# CLK_INPUT.net
KiCad netlist of a schematic drawn in Altium Designer
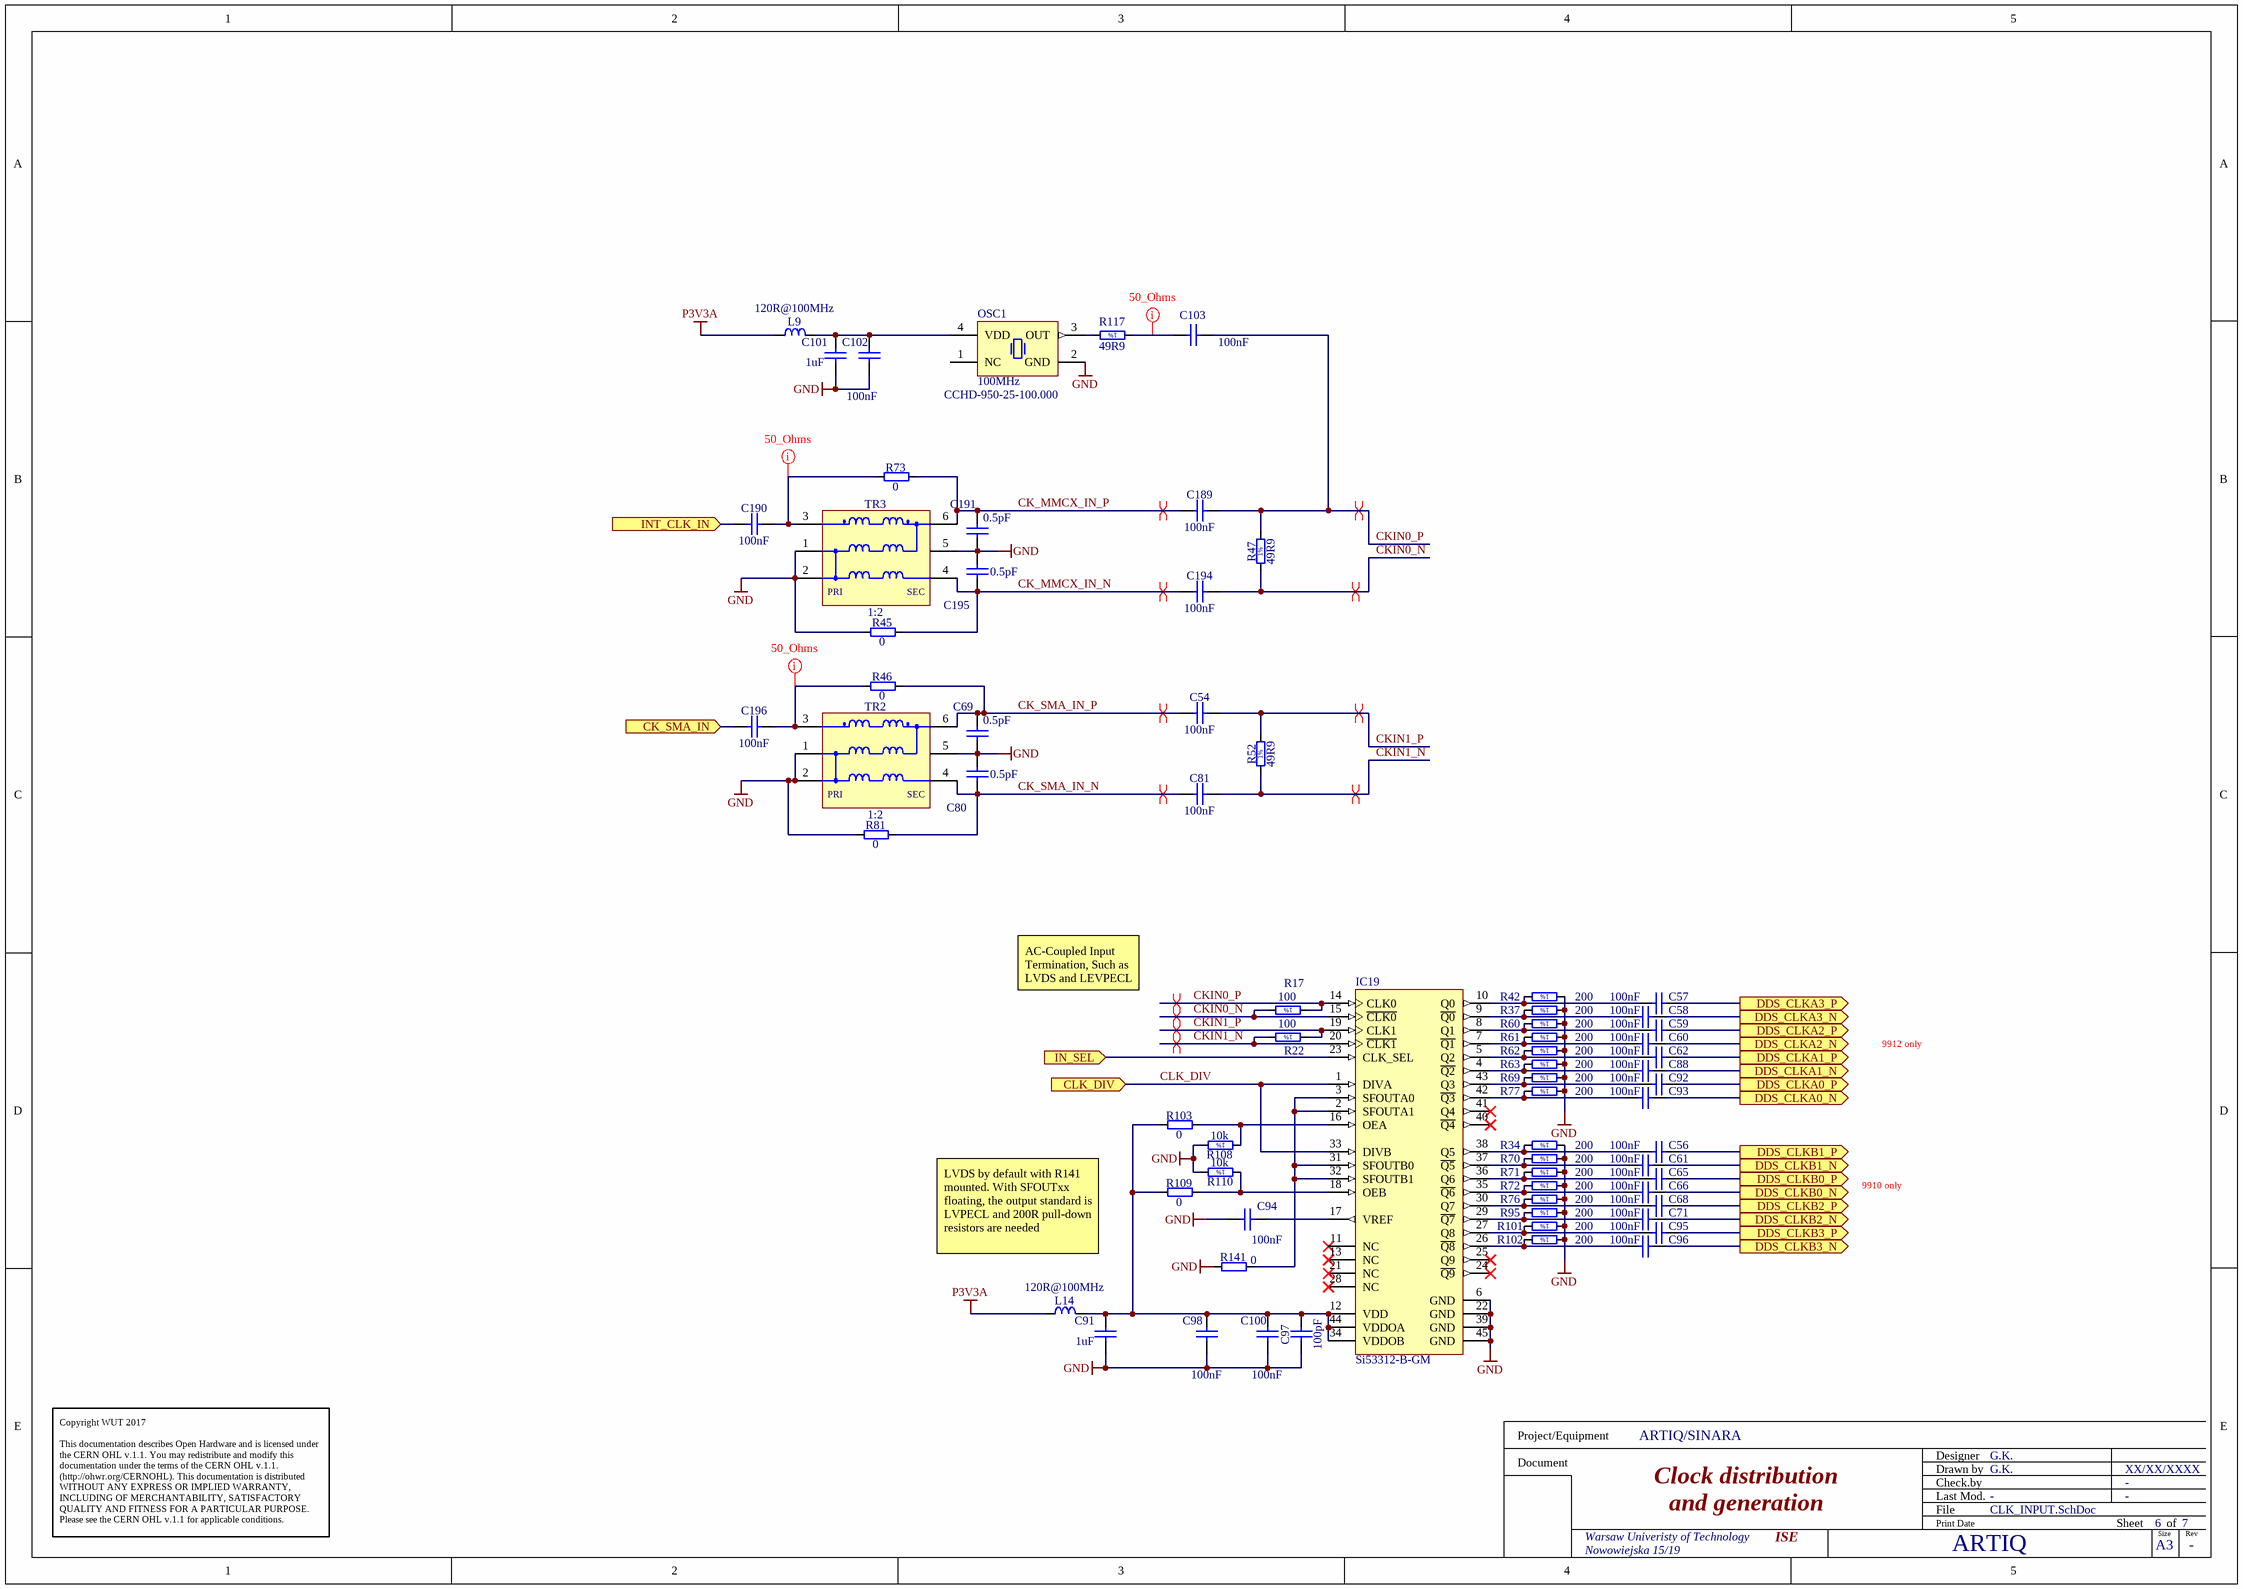
[diagram p0: CLK_INPUT.SchDoc]

(export (version "E")
  (design (tool "Eeschema 10.0.6"))
  (components
    (comp (ref "C54")
      (value "100nF")
      (footprint "CAPC1005X55N")
      (description "Non-polarised capacitor")
      (fields
        (field (name "PART NUMBER") "CC0402_100NF_16V_10%_X5R")
        (field (name "VOLTAGE") "16V")
        (field (name "AUTHOR") "CERN DEM JLC")
      )
      (libsource (lib "Capacitors") (part "Capacitor - non polarized"))
    )
    (comp (ref "C56")
      (value "100nF")
      (footprint "CAPC1005X55N")
      (description "Non-polarised capacitor")
      (fields
        (field (name "PART NUMBER") "CC0402_100NF_16V_10%_X5R")
        (field (name "VOLTAGE") "16V")
        (field (name "AUTHOR") "CERN DEM JLC")
      )
      (libsource (lib "Capacitors") (part "Capacitor - non polarized"))
    )
    (comp (ref "C57")
      (value "100nF")
      (footprint "CAPC1005X55N")
      (description "Non-polarised capacitor")
      (fields
        (field (name "PART NUMBER") "CC0402_100NF_16V_10%_X5R")
        (field (name "VOLTAGE") "16V")
        (field (name "AUTHOR") "CERN DEM JLC")
      )
      (libsource (lib "Capacitors") (part "Capacitor - non polarized"))
    )
    (comp (ref "C58")
      (value "100nF")
      (footprint "CAPC1005X55N")
      (description "Non-polarised capacitor")
      (fields
        (field (name "PART NUMBER") "CC0402_100NF_16V_10%_X5R")
        (field (name "VOLTAGE") "16V")
        (field (name "AUTHOR") "CERN DEM JLC")
      )
      (libsource (lib "Capacitors") (part "Capacitor - non polarized"))
    )
    (comp (ref "C59")
      (value "100nF")
      (footprint "CAPC1005X55N")
      (description "Non-polarised capacitor")
      (fields
        (field (name "PART NUMBER") "CC0402_100NF_16V_10%_X5R")
        (field (name "VOLTAGE") "16V")
        (field (name "AUTHOR") "CERN DEM JLC")
      )
      (libsource (lib "Capacitors") (part "Capacitor - non polarized"))
    )
    (comp (ref "C60")
      (value "100nF")
      (footprint "CAPC1005X55N")
      (description "Non-polarised capacitor")
      (fields
        (field (name "PART NUMBER") "CC0402_100NF_16V_10%_X5R")
        (field (name "VOLTAGE") "16V")
        (field (name "AUTHOR") "CERN DEM JLC")
      )
      (libsource (lib "Capacitors") (part "Capacitor - non polarized"))
    )
    (comp (ref "C61")
      (value "100nF")
      (footprint "CAPC1005X55N")
      (description "Non-polarised capacitor")
      (fields
        (field (name "PART NUMBER") "CC0402_100NF_16V_10%_X5R")
        (field (name "VOLTAGE") "16V")
        (field (name "AUTHOR") "CERN DEM JLC")
      )
      (libsource (lib "Capacitors") (part "Capacitor - non polarized"))
    )
    (comp (ref "C62")
      (value "100nF")
      (footprint "CAPC1005X55N")
      (description "Non-polarised capacitor")
      (fields
        (field (name "PART NUMBER") "CC0402_100NF_16V_10%_X5R")
        (field (name "VOLTAGE") "16V")
        (field (name "AUTHOR") "CERN DEM JLC")
      )
      (libsource (lib "Capacitors") (part "Capacitor - non polarized"))
    )
    (comp (ref "C65")
      (value "100nF")
      (footprint "CAPC1005X55N")
      (description "Non-polarised capacitor")
      (fields
        (field (name "PART NUMBER") "CC0402_100NF_16V_10%_X5R")
        (field (name "VOLTAGE") "16V")
        (field (name "AUTHOR") "CERN DEM JLC")
      )
      (libsource (lib "Capacitors") (part "Capacitor - non polarized"))
    )
    (comp (ref "C66")
      (value "100nF")
      (footprint "CAPC1005X55N")
      (description "Non-polarised capacitor")
      (fields
        (field (name "PART NUMBER") "CC0402_100NF_16V_10%_X5R")
        (field (name "VOLTAGE") "16V")
        (field (name "AUTHOR") "CERN DEM JLC")
      )
      (libsource (lib "Capacitors") (part "Capacitor - non polarized"))
    )
    (comp (ref "C68")
      (value "100nF")
      (footprint "CAPC1005X55N")
      (description "Non-polarised capacitor")
      (fields
        (field (name "PART NUMBER") "CC0402_100NF_16V_10%_X5R")
        (field (name "VOLTAGE") "16V")
        (field (name "AUTHOR") "CERN DEM JLC")
      )
      (libsource (lib "Capacitors") (part "Capacitor - non polarized"))
    )
    (comp (ref "C69")
      (value "0.5pF")
      (footprint "CAPC1005X50N")
      (description "Non-polarised capacitor")
      (fields
        (field (name "PART NUMBER") "CC0402_0.5PF_25V_0.05PF_AVX_04023J0R5ABSTR")
        (field (name "VOLTAGE") "25V")
        (field (name "AUTHOR") "CERN DEM JLC")
      )
      (libsource (lib "Capacitors") (part "Capacitor - non polarized"))
    )
    (comp (ref "C71")
      (value "100nF")
      (footprint "CAPC1005X55N")
      (description "Non-polarised capacitor")
      (fields
        (field (name "PART NUMBER") "CC0402_100NF_16V_10%_X5R")
        (field (name "VOLTAGE") "16V")
        (field (name "AUTHOR") "CERN DEM JLC")
      )
      (libsource (lib "Capacitors") (part "Capacitor - non polarized"))
    )
    (comp (ref "C80")
      (value "0.5pF")
      (footprint "CAPC1005X50N")
      (description "Non-polarised capacitor")
      (fields
        (field (name "PART NUMBER") "CC0402_0.5PF_25V_0.05PF_AVX_04023J0R5ABSTR")
        (field (name "VOLTAGE") "25V")
        (field (name "AUTHOR") "CERN DEM JLC")
      )
      (libsource (lib "Capacitors") (part "Capacitor - non polarized"))
    )
    (comp (ref "C81")
      (value "100nF")
      (footprint "CAPC1005X55N")
      (description "Non-polarised capacitor")
      (fields
        (field (name "PART NUMBER") "CC0402_100NF_16V_10%_X5R")
        (field (name "VOLTAGE") "16V")
        (field (name "AUTHOR") "CERN DEM JLC")
      )
      (libsource (lib "Capacitors") (part "Capacitor - non polarized"))
    )
    (comp (ref "C88")
      (value "100nF")
      (footprint "CAPC1005X55N")
      (description "Non-polarised capacitor")
      (fields
        (field (name "PART NUMBER") "CC0402_100NF_16V_10%_X5R")
        (field (name "VOLTAGE") "16V")
        (field (name "AUTHOR") "CERN DEM JLC")
      )
      (libsource (lib "Capacitors") (part "Capacitor - non polarized"))
    )
    (comp (ref "C91")
      (value "1uF")
      (footprint "CAPC1005X55N")
      (description "Non-polarised capacitor")
      (fields
        (field (name "PART NUMBER") "CC0402_1UF_16V_10%_X5R")
        (field (name "VOLTAGE") "16V")
        (field (name "AUTHOR") "CERN DEM JLC")
      )
      (libsource (lib "Capacitors") (part "Capacitor - non polarized"))
    )
    (comp (ref "C92")
      (value "100nF")
      (footprint "CAPC1005X55N")
      (description "Non-polarised capacitor")
      (fields
        (field (name "PART NUMBER") "CC0402_100NF_16V_10%_X5R")
        (field (name "VOLTAGE") "16V")
        (field (name "AUTHOR") "CERN DEM JLC")
      )
      (libsource (lib "Capacitors") (part "Capacitor - non polarized"))
    )
    (comp (ref "C93")
      (value "100nF")
      (footprint "CAPC1005X55N")
      (description "Non-polarised capacitor")
      (fields
        (field (name "PART NUMBER") "CC0402_100NF_16V_10%_X5R")
        (field (name "VOLTAGE") "16V")
        (field (name "AUTHOR") "CERN DEM JLC")
      )
      (libsource (lib "Capacitors") (part "Capacitor - non polarized"))
    )
    (comp (ref "C94")
      (value "100nF")
      (footprint "CAPC1005X55N")
      (description "Non-polarised capacitor")
      (fields
        (field (name "PART NUMBER") "CC0402_100NF_16V_10%_X5R")
        (field (name "VOLTAGE") "16V")
        (field (name "AUTHOR") "CERN DEM JLC")
      )
      (libsource (lib "Capacitors") (part "Capacitor - non polarized"))
    )
    (comp (ref "C95")
      (value "100nF")
      (footprint "CAPC1005X55N")
      (description "Non-polarised capacitor")
      (fields
        (field (name "PART NUMBER") "CC0402_100NF_16V_10%_X5R")
        (field (name "VOLTAGE") "16V")
        (field (name "AUTHOR") "CERN DEM JLC")
      )
      (libsource (lib "Capacitors") (part "Capacitor - non polarized"))
    )
    (comp (ref "C96")
      (value "100nF")
      (footprint "CAPC1005X55N")
      (description "Non-polarised capacitor")
      (fields
        (field (name "PART NUMBER") "CC0402_100NF_16V_10%_X5R")
        (field (name "VOLTAGE") "16V")
        (field (name "AUTHOR") "CERN DEM JLC")
      )
      (libsource (lib "Capacitors") (part "Capacitor - non polarized"))
    )
    (comp (ref "C97")
      (value "100pF")
      (footprint "CAPC1005X55N")
      (description "Non-polarised capacitor")
      (fields
        (field (name "PART NUMBER") "CC0402_100PF_50V_5%_C0G")
        (field (name "VOLTAGE") "50V")
        (field (name "AUTHOR") "CERN DEM JLC")
      )
      (libsource (lib "Capacitors") (part "Capacitor - non polarized"))
    )
    (comp (ref "C98")
      (value "100nF")
      (footprint "CAPC1005X55N")
      (description "Non-polarised capacitor")
      (fields
        (field (name "PART NUMBER") "CC0402_100NF_16V_10%_X5R")
        (field (name "VOLTAGE") "16V")
        (field (name "AUTHOR") "CERN DEM JLC")
      )
      (libsource (lib "Capacitors") (part "Capacitor - non polarized"))
    )
    (comp (ref "C100")
      (value "100nF")
      (footprint "CAPC1005X55N")
      (description "Non-polarised capacitor")
      (fields
        (field (name "PART NUMBER") "CC0402_100NF_16V_10%_X5R")
        (field (name "VOLTAGE") "16V")
        (field (name "AUTHOR") "CERN DEM JLC")
      )
      (libsource (lib "Capacitors") (part "Capacitor - non polarized"))
    )
    (comp (ref "C101")
      (value "1uF")
      (footprint "CAPC1005X55N")
      (description "Non-polarised capacitor")
      (fields
        (field (name "PART NUMBER") "CC0402_1UF_16V_10%_X5R")
        (field (name "VOLTAGE") "16V")
        (field (name "AUTHOR") "CERN DEM JLC")
      )
      (libsource (lib "Capacitors") (part "Capacitor - non polarized"))
    )
    (comp (ref "C102")
      (value "100nF")
      (footprint "CAPC1005X55N")
      (description "Non-polarised capacitor")
      (fields
        (field (name "PART NUMBER") "CC0402_100NF_16V_10%_X5R")
        (field (name "VOLTAGE") "16V")
        (field (name "AUTHOR") "CERN DEM JLC")
      )
      (libsource (lib "Capacitors") (part "Capacitor - non polarized"))
    )
    (comp (ref "C103")
      (value "100nF")
      (footprint "CAPC1005X55N")
      (description "Non-polarised capacitor")
      (fields
        (field (name "PART NUMBER") "CC0402_100NF_16V_10%_X5R")
        (field (name "VOLTAGE") "16V")
        (field (name "AUTHOR") "CERN DEM JLC")
      )
      (libsource (lib "Capacitors") (part "Capacitor - non polarized"))
    )
    (comp (ref "C189")
      (value "100nF")
      (footprint "CAPC1005X55N")
      (description "Non-polarised capacitor")
      (fields
        (field (name "PART NUMBER") "CC0402_100NF_16V_10%_X5R")
        (field (name "VOLTAGE") "16V")
        (field (name "AUTHOR") "CERN DEM JLC")
      )
      (libsource (lib "Capacitors") (part "Capacitor - non polarized"))
    )
    (comp (ref "C190")
      (value "100nF")
      (footprint "CAPC1005X55N")
      (description "Non-polarised capacitor")
      (fields
        (field (name "PART NUMBER") "CC0402_100NF_16V_10%_X5R")
        (field (name "VOLTAGE") "16V")
        (field (name "AUTHOR") "CERN DEM JLC")
      )
      (libsource (lib "Capacitors") (part "Capacitor - non polarized"))
    )
    (comp (ref "C191")
      (value "0.5pF")
      (footprint "CAPC1005X50N")
      (description "Non-polarised capacitor")
      (fields
        (field (name "PART NUMBER") "CC0402_0.5PF_25V_0.05PF_AVX_04023J0R5ABSTR")
        (field (name "VOLTAGE") "25V")
        (field (name "AUTHOR") "CERN DEM JLC")
      )
      (libsource (lib "Capacitors") (part "Capacitor - non polarized"))
    )
    (comp (ref "C194")
      (value "100nF")
      (footprint "CAPC1005X55N")
      (description "Non-polarised capacitor")
      (fields
        (field (name "PART NUMBER") "CC0402_100NF_16V_10%_X5R")
        (field (name "VOLTAGE") "16V")
        (field (name "AUTHOR") "CERN DEM JLC")
      )
      (libsource (lib "Capacitors") (part "Capacitor - non polarized"))
    )
    (comp (ref "C195")
      (value "0.5pF")
      (footprint "CAPC1005X50N")
      (description "Non-polarised capacitor")
      (fields
        (field (name "PART NUMBER") "CC0402_0.5PF_25V_0.05PF_AVX_04023J0R5ABSTR")
        (field (name "VOLTAGE") "25V")
        (field (name "AUTHOR") "CERN DEM JLC")
      )
      (libsource (lib "Capacitors") (part "Capacitor - non polarized"))
    )
    (comp (ref "C196")
      (value "100nF")
      (footprint "CAPC1005X55N")
      (description "Non-polarised capacitor")
      (fields
        (field (name "PART NUMBER") "CC0402_100NF_16V_10%_X5R")
        (field (name "VOLTAGE") "16V")
        (field (name "AUTHOR") "CERN DEM JLC")
      )
      (libsource (lib "Capacitors") (part "Capacitor - non polarized"))
    )
    (comp (ref "IC19")
      (value "Si53312-B-GM")
      (footprint "SLAB-QFN-44-2800x2800TP_N")
      (fields (field (name "MANUFACTURER") "Silicon Labs"))
      (libsource (lib "Altium Content Vault") (part "SLAB-Si53312-QFN-44-45"))
    )
    (comp (ref "L9")
      (value "120R@100MHz")
      (footprint "INDC1608X95N")
      (description "Inductor")
      (fields
        (field (name "PART NUMBER") "IND0603_MURATA_BLM18PG121SN1D")
        (field (name "POWER") "2A")
        (field (name "AUTHOR") "CERN DEM BC")
      )
      (libsource (lib "Inductors & Transformers") (part "Inductor"))
    )
    (comp (ref "L14")
      (value "120R@100MHz")
      (footprint "INDC1608X95N")
      (description "Inductor")
      (fields
        (field (name "PART NUMBER") "IND0603_MURATA_BLM18PG121SN1D")
        (field (name "POWER") "2A")
        (field (name "AUTHOR") "CERN DEM BC")
      )
      (libsource (lib "Inductors & Transformers") (part "Inductor"))
    )
    (comp (ref "OSC1")
      (value "100MHz")
      (footprint "OSC_CRYSTEK_CCHD-950")
      (description "100MHz low noise oscillator")
      (fields
        (field (name "PART NUMBER") "OSC_100MHZ_CRYSTEK_CCHD-950-25-100.000")
        (field (name "MANUFACTURER") "CRYSTEK CRYSTAL")
        (field (name "MANUFACTURER PART NUMBER") "CCHD-950-25-100.000")
        (field (name "AUTHOR") "GK")
      )
      (libsource (lib "LIBRARY_SCH") (part "OSC_CCHD-950"))
    )
    (comp (ref "R17")
      (value "100")
      (footprint "RESC1005X40N")
      (description "Resistor - 1%")
      (fields
        (field (name "PART NUMBER") "R0402_100R_1%_0.0625W_100PPM")
        (field (name "POWER") "0.0625W")
        (field (name "AUTHOR") "CERN DEM JLC")
      )
      (libsource (lib "Resistors") (part "Resistor - 1%"))
    )
    (comp (ref "R22")
      (value "100")
      (footprint "RESC1005X40N")
      (description "Resistor - 1%")
      (fields
        (field (name "PART NUMBER") "R0402_100R_1%_0.0625W_100PPM")
        (field (name "POWER") "0.0625W")
        (field (name "AUTHOR") "CERN DEM JLC")
      )
      (libsource (lib "Resistors") (part "Resistor - 1%"))
    )
    (comp (ref "R34")
      (value "200")
      (footprint "RESC1005X40N")
      (description "Resistor - 1%")
      (fields
        (field (name "PART NUMBER") "R0402_200R_1%_0.0625W_100PPM")
        (field (name "POWER") "0.0625W")
        (field (name "AUTHOR") "CERN DEM JLC")
      )
      (libsource (lib "Resistors") (part "Resistor - 1%"))
    )
    (comp (ref "R37")
      (value "200")
      (footprint "RESC1005X40N")
      (description "Resistor - 1%")
      (fields
        (field (name "PART NUMBER") "R0402_200R_1%_0.0625W_100PPM")
        (field (name "POWER") "0.0625W")
        (field (name "AUTHOR") "CERN DEM JLC")
      )
      (libsource (lib "Resistors") (part "Resistor - 1%"))
    )
    (comp (ref "R42")
      (value "200")
      (footprint "RESC1005X40N")
      (description "Resistor - 1%")
      (fields
        (field (name "PART NUMBER") "R0402_200R_1%_0.0625W_100PPM")
        (field (name "POWER") "0.0625W")
        (field (name "AUTHOR") "CERN DEM JLC")
      )
      (libsource (lib "Resistors") (part "Resistor - 1%"))
    )
    (comp (ref "R45")
      (value "0")
      (footprint "RESC1005X40N")
      (description "Resistor")
      (fields
        (field (name "PART NUMBER") "R0402_0R_JUMPER")
        (field (name "MANUFACTURER") "GENERIC")
        (field (name "AUTHOR") "CERN DEM JLC")
      )
      (libsource (lib "Resistors") (part "Resistor"))
    )
    (comp (ref "R46")
      (value "0")
      (footprint "RESC1005X40N")
      (description "Resistor")
      (fields
        (field (name "PART NUMBER") "R0402_0R_JUMPER")
        (field (name "MANUFACTURER") "GENERIC")
        (field (name "AUTHOR") "CERN DEM JLC")
      )
      (libsource (lib "Resistors") (part "Resistor"))
    )
    (comp (ref "R47")
      (value "49R9")
      (footprint "RESC1005X40N")
      (description "Resistor - 1%")
      (fields
        (field (name "PART NUMBER") "R0402_49R9_1%_0.0625W_100PPM")
        (field (name "POWER") "0.0625W")
        (field (name "AUTHOR") "CERN DEM JLC")
      )
      (libsource (lib "Resistors") (part "Resistor - 1%"))
    )
    (comp (ref "R52")
      (value "49R9")
      (footprint "RESC1005X40N")
      (description "Resistor - 1%")
      (fields
        (field (name "PART NUMBER") "R0402_49R9_1%_0.0625W_100PPM")
        (field (name "POWER") "0.0625W")
        (field (name "AUTHOR") "CERN DEM JLC")
      )
      (libsource (lib "Resistors") (part "Resistor - 1%"))
    )
    (comp (ref "R60")
      (value "200")
      (footprint "RESC1005X40N")
      (description "Resistor - 1%")
      (fields
        (field (name "PART NUMBER") "R0402_200R_1%_0.0625W_100PPM")
        (field (name "POWER") "0.0625W")
        (field (name "AUTHOR") "CERN DEM JLC")
      )
      (libsource (lib "Resistors") (part "Resistor - 1%"))
    )
    (comp (ref "R61")
      (value "200")
      (footprint "RESC1005X40N")
      (description "Resistor - 1%")
      (fields
        (field (name "PART NUMBER") "R0402_200R_1%_0.0625W_100PPM")
        (field (name "POWER") "0.0625W")
        (field (name "AUTHOR") "CERN DEM JLC")
      )
      (libsource (lib "Resistors") (part "Resistor - 1%"))
    )
    (comp (ref "R62")
      (value "200")
      (footprint "RESC1005X40N")
      (description "Resistor - 1%")
      (fields
        (field (name "PART NUMBER") "R0402_200R_1%_0.0625W_100PPM")
        (field (name "POWER") "0.0625W")
        (field (name "AUTHOR") "CERN DEM JLC")
      )
      (libsource (lib "Resistors") (part "Resistor - 1%"))
    )
    (comp (ref "R63")
      (value "200")
      (footprint "RESC1005X40N")
      (description "Resistor - 1%")
      (fields
        (field (name "PART NUMBER") "R0402_200R_1%_0.0625W_100PPM")
        (field (name "POWER") "0.0625W")
        (field (name "AUTHOR") "CERN DEM JLC")
      )
      (libsource (lib "Resistors") (part "Resistor - 1%"))
    )
    (comp (ref "R69")
      (value "200")
      (footprint "RESC1005X40N")
      (description "Resistor - 1%")
      (fields
        (field (name "PART NUMBER") "R0402_200R_1%_0.0625W_100PPM")
        (field (name "POWER") "0.0625W")
        (field (name "AUTHOR") "CERN DEM JLC")
      )
      (libsource (lib "Resistors") (part "Resistor - 1%"))
    )
    (comp (ref "R70")
      (value "200")
      (footprint "RESC1005X40N")
      (description "Resistor - 1%")
      (fields
        (field (name "PART NUMBER") "R0402_200R_1%_0.0625W_100PPM")
        (field (name "POWER") "0.0625W")
        (field (name "AUTHOR") "CERN DEM JLC")
      )
      (libsource (lib "Resistors") (part "Resistor - 1%"))
    )
    (comp (ref "R71")
      (value "200")
      (footprint "RESC1005X40N")
      (description "Resistor - 1%")
      (fields
        (field (name "PART NUMBER") "R0402_200R_1%_0.0625W_100PPM")
        (field (name "POWER") "0.0625W")
        (field (name "AUTHOR") "CERN DEM JLC")
      )
      (libsource (lib "Resistors") (part "Resistor - 1%"))
    )
    (comp (ref "R72")
      (value "200")
      (footprint "RESC1005X40N")
      (description "Resistor - 1%")
      (fields
        (field (name "PART NUMBER") "R0402_200R_1%_0.0625W_100PPM")
        (field (name "POWER") "0.0625W")
        (field (name "AUTHOR") "CERN DEM JLC")
      )
      (libsource (lib "Resistors") (part "Resistor - 1%"))
    )
    (comp (ref "R73")
      (value "0")
      (footprint "RESC1005X40N")
      (description "Resistor")
      (fields
        (field (name "PART NUMBER") "R0402_0R_JUMPER")
        (field (name "MANUFACTURER") "GENERIC")
        (field (name "AUTHOR") "CERN DEM JLC")
      )
      (libsource (lib "Resistors") (part "Resistor"))
    )
    (comp (ref "R76")
      (value "200")
      (footprint "RESC1005X40N")
      (description "Resistor - 1%")
      (fields
        (field (name "PART NUMBER") "R0402_200R_1%_0.0625W_100PPM")
        (field (name "POWER") "0.0625W")
        (field (name "AUTHOR") "CERN DEM JLC")
      )
      (libsource (lib "Resistors") (part "Resistor - 1%"))
    )
    (comp (ref "R77")
      (value "200")
      (footprint "RESC1005X40N")
      (description "Resistor - 1%")
      (fields
        (field (name "PART NUMBER") "R0402_200R_1%_0.0625W_100PPM")
        (field (name "POWER") "0.0625W")
        (field (name "AUTHOR") "CERN DEM JLC")
      )
      (libsource (lib "Resistors") (part "Resistor - 1%"))
    )
    (comp (ref "R81")
      (value "0")
      (footprint "RESC1005X40N")
      (description "Resistor")
      (fields
        (field (name "PART NUMBER") "R0402_0R_JUMPER")
        (field (name "MANUFACTURER") "GENERIC")
        (field (name "AUTHOR") "CERN DEM JLC")
      )
      (libsource (lib "Resistors") (part "Resistor"))
    )
    (comp (ref "R95")
      (value "200")
      (footprint "RESC1005X40N")
      (description "Resistor - 1%")
      (fields
        (field (name "PART NUMBER") "R0402_200R_1%_0.0625W_100PPM")
        (field (name "POWER") "0.0625W")
        (field (name "AUTHOR") "CERN DEM JLC")
      )
      (libsource (lib "Resistors") (part "Resistor - 1%"))
    )
    (comp (ref "R101")
      (value "200")
      (footprint "RESC1005X40N")
      (description "Resistor - 1%")
      (fields
        (field (name "PART NUMBER") "R0402_200R_1%_0.0625W_100PPM")
        (field (name "POWER") "0.0625W")
        (field (name "AUTHOR") "CERN DEM JLC")
      )
      (libsource (lib "Resistors") (part "Resistor - 1%"))
    )
    (comp (ref "R102")
      (value "200")
      (footprint "RESC1005X40N")
      (description "Resistor - 1%")
      (fields
        (field (name "PART NUMBER") "R0402_200R_1%_0.0625W_100PPM")
        (field (name "POWER") "0.0625W")
        (field (name "AUTHOR") "CERN DEM JLC")
      )
      (libsource (lib "Resistors") (part "Resistor - 1%"))
    )
    (comp (ref "R103")
      (value "0")
      (footprint "RESC1608X55N")
      (description "Resistor")
      (fields
        (field (name "PART NUMBER") "R0603_0R_JUMPER")
        (field (name "MANUFACTURER") "GENERIC")
        (field (name "AUTHOR") "CERN DEM JLC")
      )
      (libsource (lib "Resistors") (part "Resistor"))
    )
    (comp (ref "R108")
      (value "10k")
      (footprint "RESC1005X40N")
      (description "Resistor - 1%")
      (fields
        (field (name "PART NUMBER") "R0402_10K_1%_0.0625W_100PPM")
        (field (name "POWER") "0.0625W")
        (field (name "AUTHOR") "CERN DEM JLC")
      )
      (libsource (lib "Resistors") (part "Resistor - 1%"))
    )
    (comp (ref "R109")
      (value "0")
      (footprint "RESC1608X55N")
      (description "Resistor")
      (fields
        (field (name "PART NUMBER") "R0603_0R_JUMPER")
        (field (name "MANUFACTURER") "GENERIC")
        (field (name "AUTHOR") "CERN DEM JLC")
      )
      (libsource (lib "Resistors") (part "Resistor"))
    )
    (comp (ref "R110")
      (value "10k")
      (footprint "RESC1005X40N")
      (description "Resistor - 1%")
      (fields
        (field (name "PART NUMBER") "R0402_10K_1%_0.0625W_100PPM")
        (field (name "POWER") "0.0625W")
        (field (name "AUTHOR") "CERN DEM JLC")
      )
      (libsource (lib "Resistors") (part "Resistor - 1%"))
    )
    (comp (ref "R117")
      (value "49R9")
      (footprint "RESC1005X40N")
      (description "Resistor - 1%")
      (fields
        (field (name "PART NUMBER") "R0402_49R9_1%_0.0625W_100PPM")
        (field (name "POWER") "0.0625W")
        (field (name "AUTHOR") "CERN DEM JLC")
      )
      (libsource (lib "Resistors") (part "Resistor - 1%"))
    )
    (comp (ref "R141")
      (value "0")
      (footprint "RESC1608X55N")
      (description "Resistor")
      (fields
        (field (name "PART NUMBER") "R0603_0R_JUMPER")
        (field (name "MANUFACTURER") "GENERIC")
        (field (name "AUTHOR") "CERN DEM JLC")
      )
      (libsource (lib "Resistors") (part "Resistor"))
    )
    (comp (ref "TR2")
      (value "1:2")
      (footprint "XFMR_MINI-CIRCUITS_DB1627")
      (description "50 OHMS 10 to 4000 MHz RF Transformer")
      (fields
        (field (name "PART NUMBER") "XFMR_MINI-CIRCUITS_TCM2-43X+")
        (field (name "POWER") "0.4W")
        (field (name "AUTHOR") "CERN DEM BC")
      )
      (libsource (lib "Inductors & Transformers") (part "XFMR_MINI-CIRCUITS_TCM2-43X"))
    )
    (comp (ref "TR3")
      (value "1:2")
      (footprint "XFMR_MINI-CIRCUITS_DB1627")
      (description "50 OHMS 10 to 4000 MHz RF Transformer")
      (fields
        (field (name "PART NUMBER") "XFMR_MINI-CIRCUITS_TCM2-43X+")
        (field (name "POWER") "0.4W")
        (field (name "AUTHOR") "CERN DEM BC")
      )
      (libsource (lib "Inductors & Transformers") (part "XFMR_MINI-CIRCUITS_TCM2-43X"))
    )
  )
  (nets
    (net (code "1") (name "/CKIN0_N") (class "Default")
      (node (ref "C194") (pin "2") (pinfunction "2_2") (pintype "passive"))
      (node (ref "IC19") (pin "15") (pinfunction "~{CLK0}_15") (pintype "input"))
      (node (ref "R17") (pin "2") (pinfunction "2_2") (pintype "passive"))
      (node (ref "R47") (pin "1") (pinfunction "1_1") (pintype "passive"))
    )
    (net (code "2") (name "/CKIN0_P") (class "Default")
      (node (ref "C103") (pin "1") (pinfunction "1_1") (pintype "passive"))
      (node (ref "C189") (pin "2") (pinfunction "2_2") (pintype "passive"))
      (node (ref "IC19") (pin "14") (pinfunction "CLK0_14") (pintype "input"))
      (node (ref "R17") (pin "1") (pinfunction "1_1") (pintype "passive"))
      (node (ref "R47") (pin "2") (pinfunction "2_2") (pintype "passive"))
    )
    (net (code "3") (name "/CKIN1_N") (class "Default")
      (node (ref "C81") (pin "2") (pinfunction "2_2") (pintype "passive"))
      (node (ref "IC19") (pin "20") (pinfunction "~{CLK1}_20") (pintype "input"))
      (node (ref "R22") (pin "2") (pinfunction "2_2") (pintype "passive"))
      (node (ref "R52") (pin "1") (pinfunction "1_1") (pintype "passive"))
    )
    (net (code "4") (name "/CKIN1_P") (class "Default")
      (node (ref "C54") (pin "2") (pinfunction "2_2") (pintype "passive"))
      (node (ref "IC19") (pin "19") (pinfunction "CLK1_19") (pintype "input"))
      (node (ref "R22") (pin "1") (pinfunction "1_1") (pintype "passive"))
      (node (ref "R52") (pin "2") (pinfunction "2_2") (pintype "passive"))
    )
    (net (code "5") (name "/CK_MMCX_IN_N") (class "Default")
      (node (ref "C194") (pin "1") (pinfunction "1_1") (pintype "passive"))
      (node (ref "C195") (pin "1") (pinfunction "1_1") (pintype "passive"))
      (node (ref "R45") (pin "2") (pinfunction "2_2") (pintype "passive"))
      (node (ref "TR3") (pin "4") (pinfunction "S1_4") (pintype "passive"))
    )
    (net (code "6") (name "/CK_MMCX_IN_P") (class "Default")
      (node (ref "C189") (pin "1") (pinfunction "1_1") (pintype "passive"))
      (node (ref "C191") (pin "2") (pinfunction "2_2") (pintype "passive"))
      (node (ref "R73") (pin "2") (pinfunction "2_2") (pintype "passive"))
      (node (ref "TR3") (pin "6") (pinfunction "S1_6") (pintype "passive"))
    )
    (net (code "7") (name "/CK_SMA_IN") (class "Default")
      (node (ref "C196") (pin "1") (pinfunction "1_1") (pintype "passive"))
    )
    (net (code "8") (name "/CK_SMA_IN_N") (class "Default")
      (node (ref "C80") (pin "1") (pinfunction "1_1") (pintype "passive"))
      (node (ref "C81") (pin "1") (pinfunction "1_1") (pintype "passive"))
      (node (ref "R81") (pin "2") (pinfunction "2_2") (pintype "passive"))
      (node (ref "TR2") (pin "4") (pinfunction "S1_4") (pintype "passive"))
    )
    (net (code "9") (name "/CK_SMA_IN_P") (class "Default")
      (node (ref "C54") (pin "1") (pinfunction "1_1") (pintype "passive"))
      (node (ref "C69") (pin "2") (pinfunction "2_2") (pintype "passive"))
      (node (ref "R46") (pin "2") (pinfunction "2_2") (pintype "passive"))
      (node (ref "TR2") (pin "6") (pinfunction "S1_6") (pintype "passive"))
    )
    (net (code "10") (name "/CLK_DIV") (class "Default")
      (node (ref "IC19") (pin "1") (pinfunction "DIVA_1") (pintype "input"))
      (node (ref "IC19") (pin "33") (pinfunction "DIVB_33") (pintype "input"))
    )
    (net (code "11") (name "/DDS_CLKA0_N") (class "Default")
      (node (ref "C93") (pin "1") (pinfunction "1_1") (pintype "passive"))
    )
    (net (code "12") (name "/DDS_CLKA0_P") (class "Default")
      (node (ref "C92") (pin "1") (pinfunction "1_1") (pintype "passive"))
    )
    (net (code "13") (name "/DDS_CLKA1_N") (class "Default")
      (node (ref "C88") (pin "1") (pinfunction "1_1") (pintype "passive"))
    )
    (net (code "14") (name "/DDS_CLKA1_P") (class "Default")
      (node (ref "C62") (pin "1") (pinfunction "1_1") (pintype "passive"))
    )
    (net (code "15") (name "/DDS_CLKA2_N") (class "Default")
      (node (ref "C60") (pin "1") (pinfunction "1_1") (pintype "passive"))
    )
    (net (code "16") (name "/DDS_CLKA2_P") (class "Default")
      (node (ref "C59") (pin "1") (pinfunction "1_1") (pintype "passive"))
    )
    (net (code "17") (name "/DDS_CLKA3_N") (class "Default")
      (node (ref "C58") (pin "1") (pinfunction "1_1") (pintype "passive"))
    )
    (net (code "18") (name "/DDS_CLKA3_P") (class "Default")
      (node (ref "C57") (pin "1") (pinfunction "1_1") (pintype "passive"))
    )
    (net (code "19") (name "/DDS_CLKB0_N") (class "Default")
      (node (ref "C66") (pin "1") (pinfunction "1_1") (pintype "passive"))
    )
    (net (code "20") (name "/DDS_CLKB0_P") (class "Default")
      (node (ref "C65") (pin "1") (pinfunction "1_1") (pintype "passive"))
    )
    (net (code "21") (name "/DDS_CLKB1_N") (class "Default")
      (node (ref "C61") (pin "1") (pinfunction "1_1") (pintype "passive"))
    )
    (net (code "22") (name "/DDS_CLKB1_P") (class "Default")
      (node (ref "C56") (pin "1") (pinfunction "1_1") (pintype "passive"))
    )
    (net (code "23") (name "/DDS_CLKB2_N") (class "Default")
      (node (ref "C71") (pin "1") (pinfunction "1_1") (pintype "passive"))
    )
    (net (code "24") (name "/DDS_CLKB2_P") (class "Default")
      (node (ref "C68") (pin "1") (pinfunction "1_1") (pintype "passive"))
    )
    (net (code "25") (name "/DDS_CLKB3_N") (class "Default")
      (node (ref "C96") (pin "1") (pinfunction "1_1") (pintype "passive"))
    )
    (net (code "26") (name "/DDS_CLKB3_P") (class "Default")
      (node (ref "C95") (pin "1") (pinfunction "1_1") (pintype "passive"))
    )
    (net (code "27") (name "/INT_CLK_IN") (class "Default")
      (node (ref "C190") (pin "1") (pinfunction "1_1") (pintype "passive"))
    )
    (net (code "28") (name "/IN_SEL") (class "Default")
      (node (ref "IC19") (pin "23") (pinfunction "CLK_SEL_23") (pintype "input"))
    )
    (net (code "29") (name "GND") (class "Default")
      (node (ref "C100") (pin "1") (pinfunction "1_1") (pintype "passive"))
      (node (ref "C101") (pin "1") (pinfunction "1_1") (pintype "passive"))
      (node (ref "C102") (pin "1") (pinfunction "1_1") (pintype "passive"))
      (node (ref "C191") (pin "1") (pinfunction "1_1") (pintype "passive"))
      (node (ref "C195") (pin "2") (pinfunction "2_2") (pintype "passive"))
      (node (ref "C69") (pin "1") (pinfunction "1_1") (pintype "passive"))
      (node (ref "C80") (pin "2") (pinfunction "2_2") (pintype "passive"))
      (node (ref "C91") (pin "1") (pinfunction "1_1") (pintype "passive"))
      (node (ref "C94") (pin "1") (pinfunction "1_1") (pintype "passive"))
      (node (ref "C97") (pin "1") (pinfunction "1_1") (pintype "passive"))
      (node (ref "C98") (pin "1") (pinfunction "1_1") (pintype "passive"))
      (node (ref "IC19") (pin "22") (pinfunction "GND_22") (pintype "power_in"))
      (node (ref "IC19") (pin "39") (pinfunction "GND_39") (pintype "power_in"))
      (node (ref "IC19") (pin "45") (pinfunction "GND_45") (pintype "power_in"))
      (node (ref "IC19") (pin "6") (pinfunction "GND_6") (pintype "power_in"))
      (node (ref "OSC1") (pin "2") (pinfunction "GND_2") (pintype "power_in"))
      (node (ref "R101") (pin "1") (pinfunction "1_1") (pintype "passive"))
      (node (ref "R102") (pin "1") (pinfunction "1_1") (pintype "passive"))
      (node (ref "R108") (pin "2") (pinfunction "2_2") (pintype "passive"))
      (node (ref "R110") (pin "2") (pinfunction "2_2") (pintype "passive"))
      (node (ref "R141") (pin "1") (pinfunction "1_1") (pintype "passive"))
      (node (ref "R34") (pin "1") (pinfunction "1_1") (pintype "passive"))
      (node (ref "R37") (pin "1") (pinfunction "1_1") (pintype "passive"))
      (node (ref "R42") (pin "1") (pinfunction "1_1") (pintype "passive"))
      (node (ref "R45") (pin "1") (pinfunction "1_1") (pintype "passive"))
      (node (ref "R60") (pin "1") (pinfunction "1_1") (pintype "passive"))
      (node (ref "R61") (pin "1") (pinfunction "1_1") (pintype "passive"))
      (node (ref "R62") (pin "1") (pinfunction "1_1") (pintype "passive"))
      (node (ref "R63") (pin "1") (pinfunction "1_1") (pintype "passive"))
      (node (ref "R69") (pin "1") (pinfunction "1_1") (pintype "passive"))
      (node (ref "R70") (pin "1") (pinfunction "1_1") (pintype "passive"))
      (node (ref "R71") (pin "1") (pinfunction "1_1") (pintype "passive"))
      (node (ref "R72") (pin "1") (pinfunction "1_1") (pintype "passive"))
      (node (ref "R76") (pin "1") (pinfunction "1_1") (pintype "passive"))
      (node (ref "R77") (pin "1") (pinfunction "1_1") (pintype "passive"))
      (node (ref "R81") (pin "1") (pinfunction "1_1") (pintype "passive"))
      (node (ref "R95") (pin "1") (pinfunction "1_1") (pintype "passive"))
      (node (ref "TR2") (pin "1") (pinfunction "P1_1") (pintype "passive"))
      (node (ref "TR2") (pin "2") (pinfunction "P1_2") (pintype "passive"))
      (node (ref "TR2") (pin "5") (pinfunction "NC_5") (pintype "passive"))
      (node (ref "TR3") (pin "1") (pinfunction "P1_1") (pintype "passive"))
      (node (ref "TR3") (pin "2") (pinfunction "P1_2") (pintype "passive"))
      (node (ref "TR3") (pin "5") (pinfunction "NC_5") (pintype "passive"))
    )
    (net (code "30") (name "Net-(C103-Pad2)") (class "Default")
      (node (ref "C103") (pin "2") (pinfunction "2_2") (pintype "passive"))
      (node (ref "R117") (pin "1") (pinfunction "1_1") (pintype "passive"))
    )
    (net (code "31") (name "Net-(C190-Pad2)") (class "Default")
      (node (ref "C190") (pin "2") (pinfunction "2_2") (pintype "passive"))
      (node (ref "R73") (pin "1") (pinfunction "1_1") (pintype "passive"))
      (node (ref "TR3") (pin "3") (pinfunction "P1_3") (pintype "passive"))
    )
    (net (code "32") (name "Net-(C196-Pad2)") (class "Default")
      (node (ref "C196") (pin "2") (pinfunction "2_2") (pintype "passive"))
      (node (ref "R46") (pin "1") (pinfunction "1_1") (pintype "passive"))
      (node (ref "TR2") (pin "3") (pinfunction "P1_3") (pintype "passive"))
    )
    (net (code "33") (name "Net-(IC19-OEA)") (class "Default")
      (node (ref "IC19") (pin "16") (pinfunction "OEA_16") (pintype "input"))
      (node (ref "R103") (pin "2") (pinfunction "2_2") (pintype "passive"))
      (node (ref "R108") (pin "1") (pinfunction "1_1") (pintype "passive"))
    )
    (net (code "34") (name "Net-(IC19-OEB)") (class "Default")
      (node (ref "IC19") (pin "18") (pinfunction "OEB_18") (pintype "input"))
      (node (ref "R109") (pin "2") (pinfunction "2_2") (pintype "passive"))
      (node (ref "R110") (pin "1") (pinfunction "1_1") (pintype "passive"))
    )
    (net (code "35") (name "Net-(IC19-Q0)") (class "Default")
      (node (ref "C57") (pin "2") (pinfunction "2_2") (pintype "passive"))
      (node (ref "IC19") (pin "10") (pinfunction "Q0_10") (pintype "output"))
      (node (ref "R42") (pin "2") (pinfunction "2_2") (pintype "passive"))
    )
    (net (code "36") (name "Net-(IC19-Q1)") (class "Default")
      (node (ref "C59") (pin "2") (pinfunction "2_2") (pintype "passive"))
      (node (ref "IC19") (pin "8") (pinfunction "Q1_8") (pintype "output"))
      (node (ref "R60") (pin "2") (pinfunction "2_2") (pintype "passive"))
    )
    (net (code "37") (name "Net-(IC19-Q2)") (class "Default")
      (node (ref "C62") (pin "2") (pinfunction "2_2") (pintype "passive"))
      (node (ref "IC19") (pin "5") (pinfunction "Q2_5") (pintype "output"))
      (node (ref "R62") (pin "2") (pinfunction "2_2") (pintype "passive"))
    )
    (net (code "38") (name "Net-(IC19-Q3)") (class "Default")
      (node (ref "C92") (pin "2") (pinfunction "2_2") (pintype "passive"))
      (node (ref "IC19") (pin "43") (pinfunction "Q3_43") (pintype "output"))
      (node (ref "R69") (pin "2") (pinfunction "2_2") (pintype "passive"))
    )
    (net (code "39") (name "Net-(IC19-Q5)") (class "Default")
      (node (ref "C56") (pin "2") (pinfunction "2_2") (pintype "passive"))
      (node (ref "IC19") (pin "38") (pinfunction "Q5_38") (pintype "output"))
      (node (ref "R34") (pin "2") (pinfunction "2_2") (pintype "passive"))
    )
    (net (code "40") (name "Net-(IC19-Q6)") (class "Default")
      (node (ref "C65") (pin "2") (pinfunction "2_2") (pintype "passive"))
      (node (ref "IC19") (pin "36") (pinfunction "Q6_36") (pintype "output"))
      (node (ref "R71") (pin "2") (pinfunction "2_2") (pintype "passive"))
    )
    (net (code "41") (name "Net-(IC19-Q7)") (class "Default")
      (node (ref "C68") (pin "2") (pinfunction "2_2") (pintype "passive"))
      (node (ref "IC19") (pin "30") (pinfunction "Q7_30") (pintype "output"))
      (node (ref "R76") (pin "2") (pinfunction "2_2") (pintype "passive"))
    )
    (net (code "42") (name "Net-(IC19-Q8)") (class "Default")
      (node (ref "C95") (pin "2") (pinfunction "2_2") (pintype "passive"))
      (node (ref "IC19") (pin "27") (pinfunction "Q8_27") (pintype "output"))
      (node (ref "R101") (pin "2") (pinfunction "2_2") (pintype "passive"))
    )
    (net (code "43") (name "Net-(IC19-SFOUTA0)") (class "Default")
      (node (ref "IC19") (pin "2") (pinfunction "SFOUTA1_2") (pintype "input"))
      (node (ref "IC19") (pin "3") (pinfunction "SFOUTA0_3") (pintype "input"))
      (node (ref "IC19") (pin "31") (pinfunction "SFOUTB0_31") (pintype "input"))
      (node (ref "IC19") (pin "32") (pinfunction "SFOUTB1_32") (pintype "input"))
      (node (ref "R141") (pin "2") (pinfunction "2_2") (pintype "passive"))
    )
    (net (code "44") (name "Net-(IC19-VDD)") (class "Default")
      (node (ref "C100") (pin "2") (pinfunction "2_2") (pintype "passive"))
      (node (ref "C91") (pin "2") (pinfunction "2_2") (pintype "passive"))
      (node (ref "C97") (pin "2") (pinfunction "2_2") (pintype "passive"))
      (node (ref "C98") (pin "2") (pinfunction "2_2") (pintype "passive"))
      (node (ref "IC19") (pin "12") (pinfunction "VDD_12") (pintype "power_in"))
      (node (ref "IC19") (pin "34") (pinfunction "VDDOB_34") (pintype "power_in"))
      (node (ref "IC19") (pin "44") (pinfunction "VDDOA_44") (pintype "power_in"))
      (node (ref "L14") (pin "1") (pinfunction "1_1") (pintype "passive"))
      (node (ref "R103") (pin "1") (pinfunction "1_1") (pintype "passive"))
      (node (ref "R109") (pin "1") (pinfunction "1_1") (pintype "passive"))
    )
    (net (code "45") (name "Net-(IC19-VREF)") (class "Default")
      (node (ref "C94") (pin "2") (pinfunction "2_2") (pintype "passive"))
      (node (ref "IC19") (pin "17") (pinfunction "VREF_17") (pintype "output"))
    )
    (net (code "46") (name "Net-(IC19-~{Q0})") (class "Default")
      (node (ref "C58") (pin "2") (pinfunction "2_2") (pintype "passive"))
      (node (ref "IC19") (pin "9") (pinfunction "~{Q0}_9") (pintype "output"))
      (node (ref "R37") (pin "2") (pinfunction "2_2") (pintype "passive"))
    )
    (net (code "47") (name "Net-(IC19-~{Q1})") (class "Default")
      (node (ref "C60") (pin "2") (pinfunction "2_2") (pintype "passive"))
      (node (ref "IC19") (pin "7") (pinfunction "~{Q1}_7") (pintype "output"))
      (node (ref "R61") (pin "2") (pinfunction "2_2") (pintype "passive"))
    )
    (net (code "48") (name "Net-(IC19-~{Q2})") (class "Default")
      (node (ref "C88") (pin "2") (pinfunction "2_2") (pintype "passive"))
      (node (ref "IC19") (pin "4") (pinfunction "~{Q2}_4") (pintype "output"))
      (node (ref "R63") (pin "2") (pinfunction "2_2") (pintype "passive"))
    )
    (net (code "49") (name "Net-(IC19-~{Q3})") (class "Default")
      (node (ref "C93") (pin "2") (pinfunction "2_2") (pintype "passive"))
      (node (ref "IC19") (pin "42") (pinfunction "~{Q3}_42") (pintype "output"))
      (node (ref "R77") (pin "2") (pinfunction "2_2") (pintype "passive"))
    )
    (net (code "50") (name "Net-(IC19-~{Q5})") (class "Default")
      (node (ref "C61") (pin "2") (pinfunction "2_2") (pintype "passive"))
      (node (ref "IC19") (pin "37") (pinfunction "~{Q5}_37") (pintype "output"))
      (node (ref "R70") (pin "2") (pinfunction "2_2") (pintype "passive"))
    )
    (net (code "51") (name "Net-(IC19-~{Q6})") (class "Default")
      (node (ref "C66") (pin "2") (pinfunction "2_2") (pintype "passive"))
      (node (ref "IC19") (pin "35") (pinfunction "~{Q6}_35") (pintype "output"))
      (node (ref "R72") (pin "2") (pinfunction "2_2") (pintype "passive"))
    )
    (net (code "52") (name "Net-(IC19-~{Q7})") (class "Default")
      (node (ref "C71") (pin "2") (pinfunction "2_2") (pintype "passive"))
      (node (ref "IC19") (pin "29") (pinfunction "~{Q7}_29") (pintype "output"))
      (node (ref "R95") (pin "2") (pinfunction "2_2") (pintype "passive"))
    )
    (net (code "53") (name "Net-(IC19-~{Q8})") (class "Default")
      (node (ref "C96") (pin "2") (pinfunction "2_2") (pintype "passive"))
      (node (ref "IC19") (pin "26") (pinfunction "~{Q8}_26") (pintype "output"))
      (node (ref "R102") (pin "2") (pinfunction "2_2") (pintype "passive"))
    )
    (net (code "54") (name "Net-(OSC1-OUT)") (class "Default")
      (node (ref "OSC1") (pin "3") (pinfunction "OUT_3") (pintype "output"))
      (node (ref "R117") (pin "2") (pinfunction "2_2") (pintype "passive"))
    )
    (net (code "55") (name "Net-(OSC1-VDD)") (class "Default")
      (node (ref "C101") (pin "2") (pinfunction "2_2") (pintype "passive"))
      (node (ref "C102") (pin "2") (pinfunction "2_2") (pintype "passive"))
      (node (ref "L9") (pin "1") (pinfunction "1_1") (pintype "passive"))
      (node (ref "OSC1") (pin "4") (pinfunction "VDD_4") (pintype "power_in"))
    )
    (net (code "56") (name "P3V3A") (class "Default")
      (node (ref "L14") (pin "2") (pinfunction "2_2") (pintype "passive"))
      (node (ref "L9") (pin "2") (pinfunction "2_2") (pintype "passive"))
    )
    (net (code "57") (name "unconnected-(IC19-NC-Pad11)") (class "Default")
      (node (ref "IC19") (pin "11") (pinfunction "NC_11") (pintype "passive+no_connect"))
    )
    (net (code "58") (name "unconnected-(IC19-NC-Pad13)") (class "Default")
      (node (ref "IC19") (pin "13") (pinfunction "NC_13") (pintype "passive+no_connect"))
    )
    (net (code "59") (name "unconnected-(IC19-NC-Pad21)") (class "Default")
      (node (ref "IC19") (pin "21") (pinfunction "NC_21") (pintype "passive+no_connect"))
    )
    (net (code "60") (name "unconnected-(IC19-NC-Pad28)") (class "Default")
      (node (ref "IC19") (pin "28") (pinfunction "NC_28") (pintype "passive+no_connect"))
    )
    (net (code "61") (name "unconnected-(IC19-Q4-Pad41)") (class "Default")
      (node (ref "IC19") (pin "41") (pinfunction "Q4_41") (pintype "output+no_connect"))
    )
    (net (code "62") (name "unconnected-(IC19-Q9-Pad25)") (class "Default")
      (node (ref "IC19") (pin "25") (pinfunction "Q9_25") (pintype "output+no_connect"))
    )
    (net (code "63") (name "unconnected-(IC19-~{Q4}-Pad40)") (class "Default")
      (node (ref "IC19") (pin "40") (pinfunction "~{Q4}_40") (pintype "output+no_connect"))
    )
    (net (code "64") (name "unconnected-(IC19-~{Q9}-Pad24)") (class "Default")
      (node (ref "IC19") (pin "24") (pinfunction "~{Q9}_24") (pintype "output+no_connect"))
    )
    (net (code "65") (name "unconnected-(OSC1-NC-Pad1)") (class "Default")
      (node (ref "OSC1") (pin "1") (pinfunction "NC_1") (pintype "passive"))
    )
  )
)
